# 01_uC.net
KiCad netlist of a schematic drawn in Altium Designer
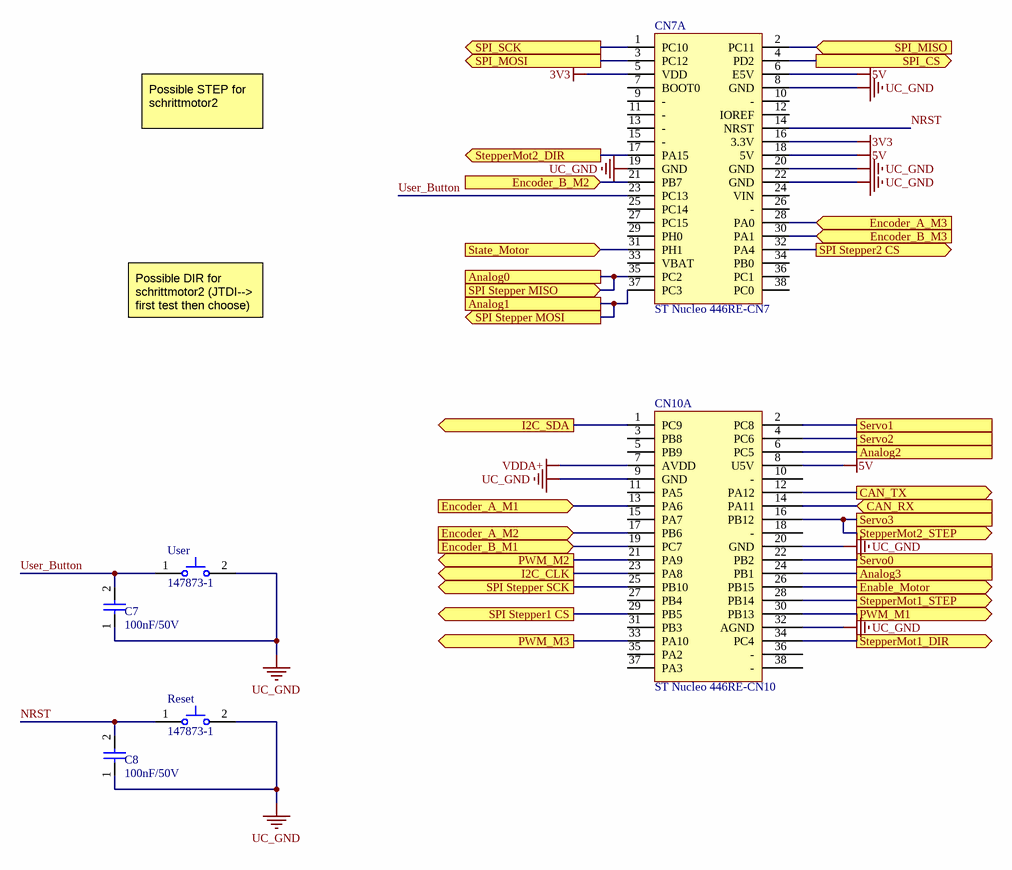
[diagram p0: 01_uC.SchDoc]

(export (version "E")
  (design (tool "Eeschema 10.0.6"))
  (components
    (comp (ref "C7")
      (value "100nF/50V")
      (footprint "CAPC1005X05L")
      (description "Cap MLCC, 100nF, 50V, X7R, 10%, 0402")
      (fields (field (name "TOLERANCE") "10%"))
      (libsource (lib "Altium Concord Pro on Altium 365") (part "CAP-NP-2"))
    )
    (comp (ref "C8")
      (value "100nF/50V")
      (footprint "CAPC1005X05L")
      (description "Cap MLCC, 100nF, 50V, X7R, 10%, 0402")
      (fields (field (name "TOLERANCE") "10%"))
      (libsource (lib "Altium Concord Pro on Altium 365") (part "CAP-NP-2"))
    )
    (comp (ref "CN7")
      (value "ST Nucleo 446RE-CN7")
      (footprint "HD254_2x19_FV_THT")
      (libsource (lib "Altium Concord Pro on Altium 365") (part "Nucleo-446RE-CN7"))
    )
    (comp (ref "CN10")
      (value "ST Nucleo 446RE-CN10")
      (footprint "HD254_2x19_FV_THT")
      (libsource (lib "Altium Concord Pro on Altium 365") (part "Nucleo-446RE-CN10"))
    )
    (comp (ref "Reset")
      (value "147873-1")
      (footprint "TE_147873-1")
      (description "Push Button, Vertical, SPST-NO, 24V, 50mA, L6B3.5H5")
      (libsource (lib "Altium Concord Pro on Altium 365") (part "SW-SPST-NO_2"))
    )
    (comp (ref "User")
      (value "147873-1")
      (footprint "TE_147873-1")
      (description "Push Button, Vertical, SPST-NO, 24V, 50mA, L6B3.5H5")
      (libsource (lib "Altium Concord Pro on Altium 365") (part "SW-SPST-NO_2"))
    )
  )
  (nets
    (net (code "1") (name "/Analog0") (class "Default")
      (node (ref "CN7") (pin "35") (pinfunction "PC2_35") (pintype "passive"))
    )
    (net (code "2") (name "/Analog1") (class "Default")
      (node (ref "CN7") (pin "37") (pinfunction "PC3_37") (pintype "passive"))
    )
    (net (code "3") (name "/Analog2") (class "Default")
      (node (ref "CN10") (pin "6") (pinfunction "PC5_6") (pintype "passive"))
    )
    (net (code "4") (name "/Analog3") (class "Default")
      (node (ref "CN10") (pin "24") (pinfunction "PB1_24") (pintype "passive"))
    )
    (net (code "5") (name "/CAN_RX") (class "Default")
      (node (ref "CN10") (pin "14") (pinfunction "PA11_14") (pintype "passive"))
    )
    (net (code "6") (name "/CAN_TX") (class "Default")
      (node (ref "CN10") (pin "12") (pinfunction "PA12_12") (pintype "passive"))
    )
    (net (code "7") (name "/Enable_Motor") (class "Default")
      (node (ref "CN10") (pin "26") (pinfunction "PB15_26") (pintype "passive"))
    )
    (net (code "8") (name "/Encoder_A_M1") (class "Default")
      (node (ref "CN10") (pin "13") (pinfunction "PA6_13") (pintype "passive"))
    )
    (net (code "9") (name "/Encoder_A_M2") (class "Default")
      (node (ref "CN10") (pin "17") (pinfunction "PB6_17") (pintype "passive"))
    )
    (net (code "10") (name "/Encoder_A_M3") (class "Default")
      (node (ref "CN7") (pin "28") (pinfunction "PA0_28") (pintype "passive"))
    )
    (net (code "11") (name "/Encoder_B_M1") (class "Default")
      (node (ref "CN10") (pin "19") (pinfunction "PC7_19") (pintype "passive"))
    )
    (net (code "12") (name "/Encoder_B_M2") (class "Default")
      (node (ref "CN7") (pin "21") (pinfunction "PB7_21") (pintype "passive"))
    )
    (net (code "13") (name "/Encoder_B_M3") (class "Default")
      (node (ref "CN7") (pin "30") (pinfunction "PA1_30") (pintype "passive"))
    )
    (net (code "14") (name "/I2C_CLK") (class "Default")
      (node (ref "CN10") (pin "23") (pinfunction "PA8_23") (pintype "passive"))
    )
    (net (code "15") (name "/I2C_SDA") (class "Default")
      (node (ref "CN10") (pin "1") (pinfunction "PC9_1") (pintype "passive"))
    )
    (net (code "16") (name "/NRST") (class "Default")
      (node (ref "C8") (pin "2") (pinfunction "2_2") (pintype "passive"))
      (node (ref "CN7") (pin "14") (pinfunction "NRST_14") (pintype "passive"))
      (node (ref "Reset") (pin "1") (pinfunction "1_1") (pintype "passive"))
    )
    (net (code "17") (name "/PWM_M1") (class "Default")
      (node (ref "CN10") (pin "30") (pinfunction "PB13_30") (pintype "passive"))
    )
    (net (code "18") (name "/PWM_M2") (class "Default")
      (node (ref "CN10") (pin "21") (pinfunction "PA9_21") (pintype "passive"))
    )
    (net (code "19") (name "/PWM_M3") (class "Default")
      (node (ref "CN10") (pin "33") (pinfunction "PA10_33") (pintype "passive"))
    )
    (net (code "20") (name "/SPI Stepper SCK") (class "Default")
      (node (ref "CN10") (pin "25") (pinfunction "PB10_25") (pintype "passive"))
    )
    (net (code "21") (name "/SPI Stepper1 CS") (class "Default")
      (node (ref "CN10") (pin "29") (pinfunction "PB5_29") (pintype "passive"))
    )
    (net (code "22") (name "/SPI Stepper2 CS") (class "Default")
      (node (ref "CN7") (pin "32") (pinfunction "PA4_32") (pintype "passive"))
    )
    (net (code "23") (name "/SPI_CS") (class "Default")
      (node (ref "CN7") (pin "4") (pinfunction "PD2_4") (pintype "passive"))
    )
    (net (code "24") (name "/SPI_MISO") (class "Default")
      (node (ref "CN7") (pin "2") (pinfunction "PC11_2") (pintype "passive"))
    )
    (net (code "25") (name "/SPI_MOSI") (class "Default")
      (node (ref "CN7") (pin "3") (pinfunction "PC12_3") (pintype "passive"))
    )
    (net (code "26") (name "/SPI_SCK") (class "Default")
      (node (ref "CN7") (pin "1") (pinfunction "PC10_1") (pintype "passive"))
    )
    (net (code "27") (name "/Servo0") (class "Default")
      (node (ref "CN10") (pin "22") (pinfunction "PB2_22") (pintype "passive"))
    )
    (net (code "28") (name "/Servo1") (class "Default")
      (node (ref "CN10") (pin "2") (pinfunction "PC8_2") (pintype "passive"))
    )
    (net (code "29") (name "/Servo2") (class "Default")
      (node (ref "CN10") (pin "4") (pinfunction "PC6_4") (pintype "passive"))
    )
    (net (code "30") (name "/Servo3") (class "Default")
      (node (ref "CN10") (pin "16") (pinfunction "PB12_16") (pintype "passive"))
    )
    (net (code "31") (name "/State_Motor") (class "Default")
      (node (ref "CN7") (pin "31") (pinfunction "PH1_31") (pintype "passive"))
    )
    (net (code "32") (name "/StepperMot1_DIR") (class "Default")
      (node (ref "CN10") (pin "34") (pinfunction "PC4_34") (pintype "passive"))
    )
    (net (code "33") (name "/StepperMot1_STEP") (class "Default")
      (node (ref "CN10") (pin "28") (pinfunction "PB14_28") (pintype "passive"))
    )
    (net (code "34") (name "/StepperMot2_DIR") (class "Default")
      (node (ref "CN7") (pin "17") (pinfunction "PA15_17") (pintype "passive"))
    )
    (net (code "35") (name "/User_Button") (class "Default")
      (node (ref "C7") (pin "2") (pinfunction "2_2") (pintype "passive"))
      (node (ref "CN7") (pin "23") (pinfunction "PC13_23") (pintype "passive"))
      (node (ref "User") (pin "1") (pinfunction "1_1") (pintype "passive"))
    )
    (net (code "36") (name "3V3") (class "Default")
      (node (ref "CN7") (pin "16") (pinfunction "3.3V_16") (pintype "power_in"))
      (node (ref "CN7") (pin "5") (pinfunction "VDD_5") (pintype "power_in"))
    )
    (net (code "37") (name "5V") (class "Default")
      (node (ref "CN10") (pin "8") (pinfunction "U5V_8") (pintype "power_in"))
      (node (ref "CN7") (pin "18") (pinfunction "5V_18") (pintype "power_in"))
      (node (ref "CN7") (pin "6") (pinfunction "E5V_6") (pintype "power_in"))
    )
    (net (code "38") (name "UC_GND") (class "Default")
      (node (ref "C7") (pin "1") (pinfunction "1_1") (pintype "passive"))
      (node (ref "C8") (pin "1") (pinfunction "1_1") (pintype "passive"))
      (node (ref "CN10") (pin "20") (pinfunction "GND_20") (pintype "passive"))
      (node (ref "CN10") (pin "32") (pinfunction "AGND_32") (pintype "passive"))
      (node (ref "CN10") (pin "9") (pinfunction "GND_9") (pintype "passive"))
      (node (ref "CN7") (pin "19") (pinfunction "GND_19") (pintype "passive"))
      (node (ref "CN7") (pin "20") (pinfunction "GND_20") (pintype "passive"))
      (node (ref "CN7") (pin "22") (pinfunction "GND_22") (pintype "passive"))
      (node (ref "CN7") (pin "8") (pinfunction "GND_8") (pintype "passive"))
      (node (ref "Reset") (pin "2") (pinfunction "2_2") (pintype "passive"))
      (node (ref "User") (pin "2") (pinfunction "2_2") (pintype "passive"))
    )
    (net (code "39") (name "VDDA+") (class "Default")
      (node (ref "CN10") (pin "7") (pinfunction "AVDD_7") (pintype "power_in"))
    )
    (net (code "40") (name "unconnected-(CN7---Pad9)") (class "Default")
      (node (ref "CN7") (pin "9") (pinfunction "-_9") (pintype "power_in"))
    )
    (net (code "41") (name "unconnected-(CN7---Pad10)") (class "Default")
      (node (ref "CN7") (pin "10") (pinfunction "-_10") (pintype "passive"))
    )
    (net (code "42") (name "unconnected-(CN7---Pad11)") (class "Default")
      (node (ref "CN7") (pin "11") (pinfunction "-_11") (pintype "power_in"))
    )
    (net (code "43") (name "unconnected-(CN7---Pad13)") (class "Default")
      (node (ref "CN7") (pin "13") (pinfunction "-_13") (pintype "power_in"))
    )
    (net (code "44") (name "unconnected-(CN7---Pad15)") (class "Default")
      (node (ref "CN7") (pin "15") (pinfunction "-_15") (pintype "power_in"))
    )
    (net (code "45") (name "unconnected-(CN7---Pad26)") (class "Default")
      (node (ref "CN7") (pin "26") (pinfunction "-_26") (pintype "power_in"))
    )
    (net (code "46") (name "unconnected-(CN7-BOOT0-Pad7)") (class "Default")
      (node (ref "CN7") (pin "7") (pinfunction "BOOT0_7") (pintype "power_in"))
    )
    (net (code "47") (name "unconnected-(CN7-IOREF-Pad12)") (class "Default")
      (node (ref "CN7") (pin "12") (pinfunction "IOREF_12") (pintype "passive"))
    )
    (net (code "48") (name "unconnected-(CN7-PB0-Pad34)") (class "Default")
      (node (ref "CN7") (pin "34") (pinfunction "PB0_34") (pintype "passive"))
    )
    (net (code "49") (name "unconnected-(CN7-PC0-Pad38)") (class "Default")
      (node (ref "CN7") (pin "38") (pinfunction "PC0_38") (pintype "passive"))
    )
    (net (code "50") (name "unconnected-(CN7-PC1-Pad36)") (class "Default")
      (node (ref "CN7") (pin "36") (pinfunction "PC1_36") (pintype "passive"))
    )
    (net (code "51") (name "unconnected-(CN7-PC14-Pad25)") (class "Default")
      (node (ref "CN7") (pin "25") (pinfunction "PC14_25") (pintype "passive"))
    )
    (net (code "52") (name "unconnected-(CN7-PC15-Pad27)") (class "Default")
      (node (ref "CN7") (pin "27") (pinfunction "PC15_27") (pintype "passive"))
    )
    (net (code "53") (name "unconnected-(CN7-PH0-Pad29)") (class "Default")
      (node (ref "CN7") (pin "29") (pinfunction "PH0_29") (pintype "passive"))
    )
    (net (code "54") (name "unconnected-(CN7-VBAT-Pad33)") (class "Default")
      (node (ref "CN7") (pin "33") (pinfunction "VBAT_33") (pintype "passive"))
    )
    (net (code "55") (name "unconnected-(CN7-VIN-Pad24)") (class "Default")
      (node (ref "CN7") (pin "24") (pinfunction "VIN_24") (pintype "power_in"))
    )
    (net (code "56") (name "unconnected-(CN10---Pad10)") (class "Default")
      (node (ref "CN10") (pin "10") (pinfunction "-_10") (pintype "passive"))
    )
    (net (code "57") (name "unconnected-(CN10---Pad18)") (class "Default")
      (node (ref "CN10") (pin "18") (pinfunction "-_18") (pintype "passive"))
    )
    (net (code "58") (name "unconnected-(CN10---Pad36)") (class "Default")
      (node (ref "CN10") (pin "36") (pinfunction "-_36") (pintype "passive"))
    )
    (net (code "59") (name "unconnected-(CN10---Pad38)") (class "Default")
      (node (ref "CN10") (pin "38") (pinfunction "-_38") (pintype "passive"))
    )
    (net (code "60") (name "unconnected-(CN10-PA2-Pad35)") (class "Default")
      (node (ref "CN10") (pin "35") (pinfunction "PA2_35") (pintype "passive"))
    )
    (net (code "61") (name "unconnected-(CN10-PA3-Pad37)") (class "Default")
      (node (ref "CN10") (pin "37") (pinfunction "PA3_37") (pintype "passive"))
    )
    (net (code "62") (name "unconnected-(CN10-PA5-Pad11)") (class "Default")
      (node (ref "CN10") (pin "11") (pinfunction "PA5_11") (pintype "passive"))
    )
    (net (code "63") (name "unconnected-(CN10-PA7-Pad15)") (class "Default")
      (node (ref "CN10") (pin "15") (pinfunction "PA7_15") (pintype "passive"))
    )
    (net (code "64") (name "unconnected-(CN10-PB3-Pad31)") (class "Default")
      (node (ref "CN10") (pin "31") (pinfunction "PB3_31") (pintype "passive"))
    )
    (net (code "65") (name "unconnected-(CN10-PB4-Pad27)") (class "Default")
      (node (ref "CN10") (pin "27") (pinfunction "PB4_27") (pintype "passive"))
    )
    (net (code "66") (name "unconnected-(CN10-PB8-Pad3)") (class "Default")
      (node (ref "CN10") (pin "3") (pinfunction "PB8_3") (pintype "passive"))
    )
    (net (code "67") (name "unconnected-(CN10-PB9-Pad5)") (class "Default")
      (node (ref "CN10") (pin "5") (pinfunction "PB9_5") (pintype "passive"))
    )
  )
)
